# Main.net
KiCad netlist of a schematic drawn in Altium Designer
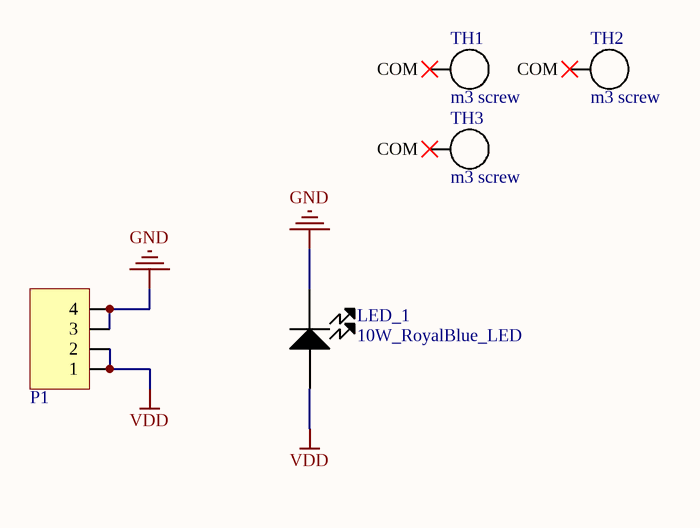
[diagram p0: Main.SchDoc]

(export (version "E")
  (design (tool "Eeschema 10.0.6"))
  (components
    (comp (ref "LED_1")
      (value "10W_RoyalBlue_LED")
      (footprint "10W_LED_200200")
      (description "445nm LED")
      (libsource (lib "ScienceComponents") (part "10W_RoyalBlue_LED"))
    )
    (comp (ref "P1")
      (value "Mini-Fit Jr 4 Pos")
      (footprint "MOLEX 0039281043")
      (libsource (lib "RSX_Connectors") (part "Molex 0039281043"))
    )
    (comp (ref "TH1")
      (value "m3 screw")
      (footprint "m3screw")
      (libsource (lib "ScienceComponents") (part "m3 screw"))
    )
    (comp (ref "TH2")
      (value "m3 screw")
      (footprint "m3screw")
      (libsource (lib "ScienceComponents") (part "m3 screw"))
    )
    (comp (ref "TH3")
      (value "m3 screw")
      (footprint "m3screw")
      (libsource (lib "ScienceComponents") (part "m3 screw"))
    )
  )
  (nets
    (net (code "1") (name "GND") (class "Default")
      (node (ref "LED_1") (pin "1") (pinfunction "-_1") (pintype "passive"))
      (node (ref "P1") (pin "3") (pinfunction "3_3") (pintype "passive"))
      (node (ref "P1") (pin "4") (pinfunction "4_4") (pintype "passive"))
    )
    (net (code "2") (name "VDD") (class "Default")
      (node (ref "LED_1") (pin "2") (pinfunction "+_2") (pintype "passive"))
      (node (ref "P1") (pin "1") (pinfunction "1_1") (pintype "passive"))
      (node (ref "P1") (pin "2") (pinfunction "2_2") (pintype "passive"))
    )
    (net (code "3") (name "unconnected-(TH1-COM-Pad0)") (class "Default")
      (node (ref "TH1") (pin "0") (pinfunction "COM_0") (pintype "passive"))
    )
    (net (code "4") (name "unconnected-(TH2-COM-Pad0)") (class "Default")
      (node (ref "TH2") (pin "0") (pinfunction "COM_0") (pintype "passive"))
    )
    (net (code "5") (name "unconnected-(TH3-COM-Pad0)") (class "Default")
      (node (ref "TH3") (pin "0") (pinfunction "COM_0") (pintype "passive"))
    )
  )
)
